# R2R.net
KiCad netlist of a schematic drawn in EAGLE
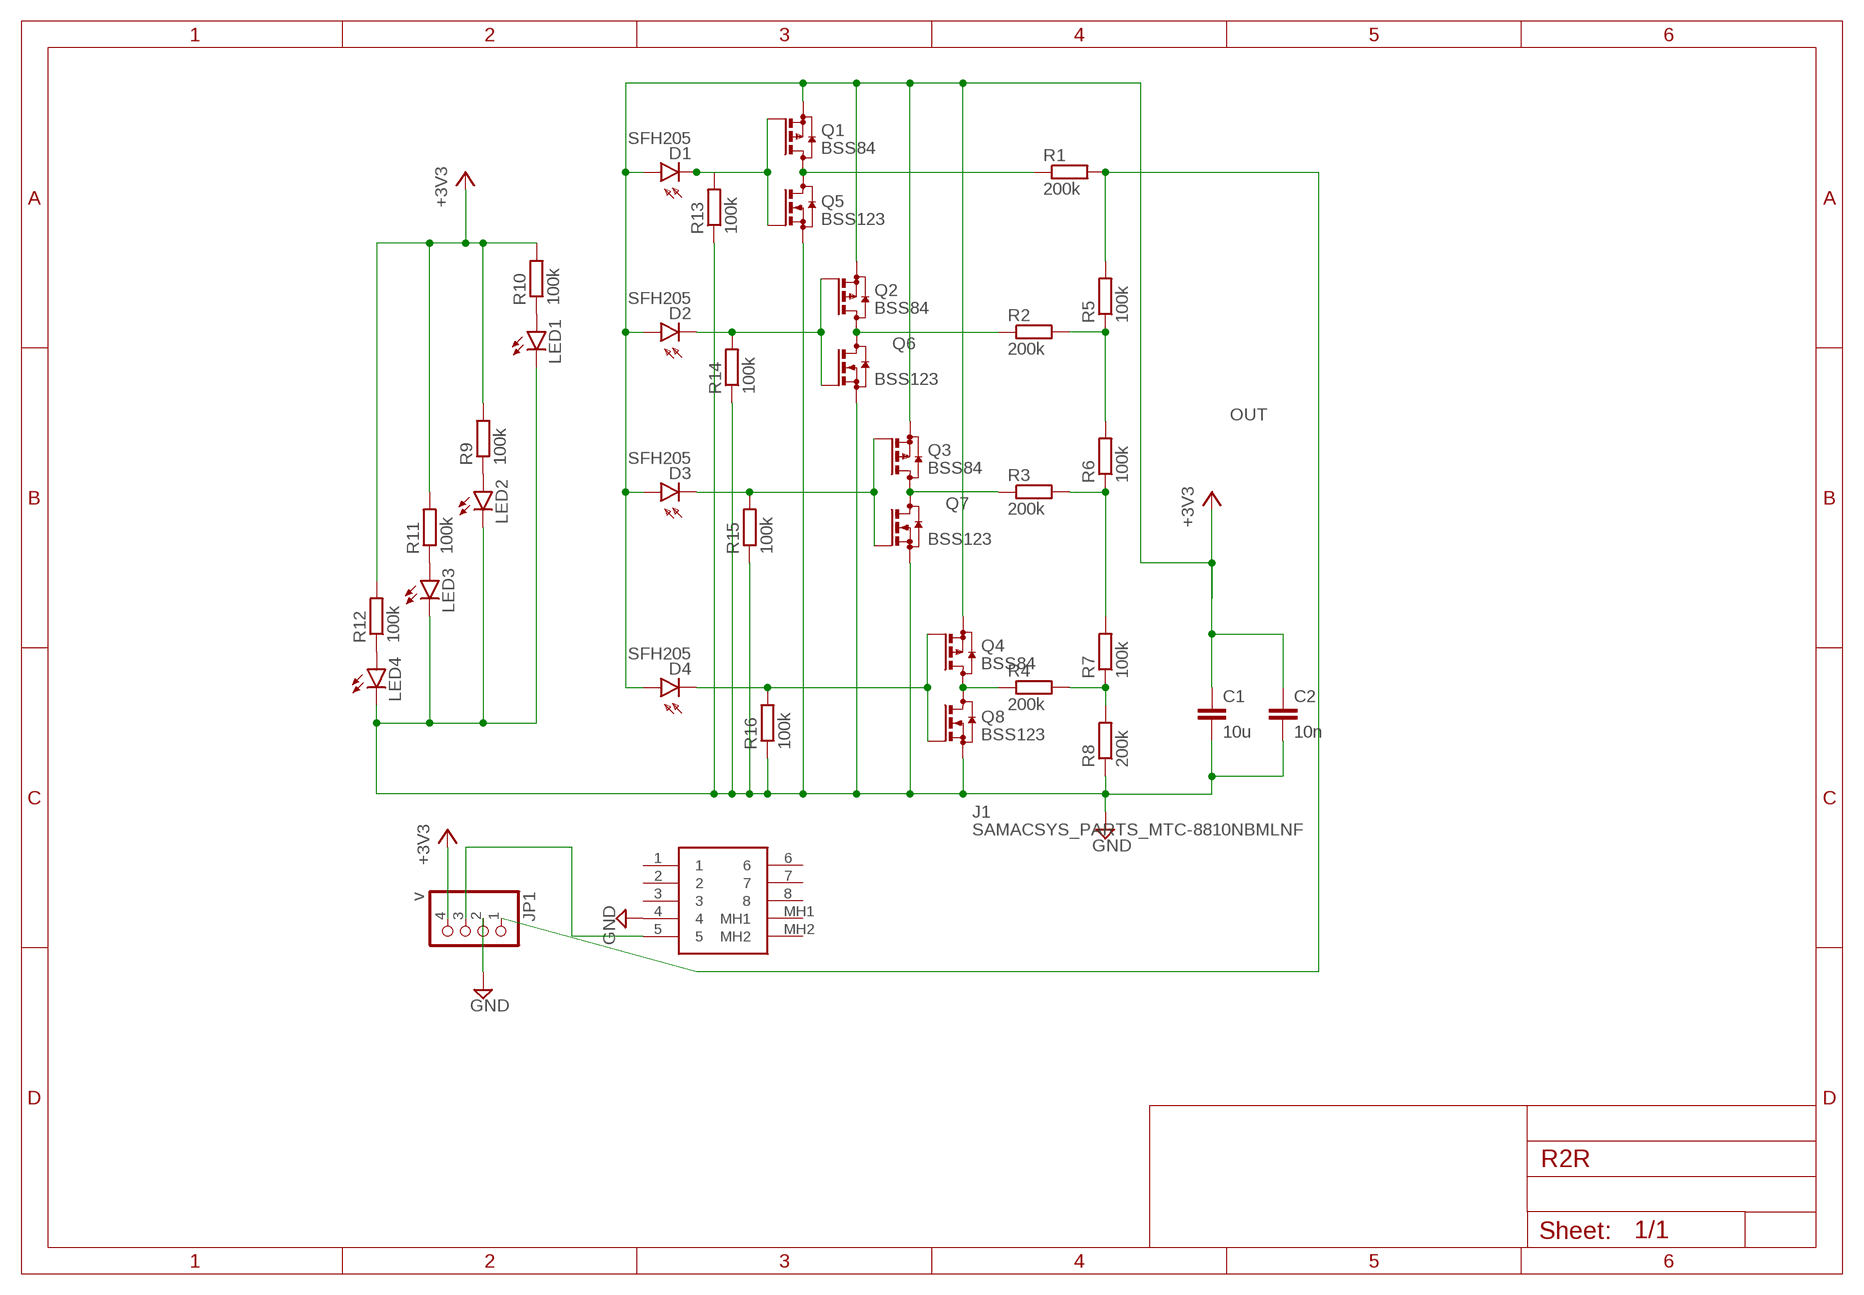
[diagram p0: schematic, sheet 1]

(export (version "E")
  (design (tool "Eeschema 10.0.6"))
  (components
    (comp (ref "C1")
      (value "10u")
      (footprint "eagle-import:C0805")
      (libsource (lib "eagle-import") (part "C-EUC0805"))
    )
    (comp (ref "C2")
      (value "10n")
      (footprint "eagle-import:C0805")
      (libsource (lib "eagle-import") (part "C-EUC0805"))
    )
    (comp (ref "D1")
      (value "SFH205")
      (footprint "eagle-import:SFH205")
      (libsource (lib "eagle-import") (part "SFH205"))
    )
    (comp (ref "D2")
      (value "SFH205")
      (footprint "eagle-import:SFH205")
      (libsource (lib "eagle-import") (part "SFH205"))
    )
    (comp (ref "D3")
      (value "SFH205")
      (footprint "eagle-import:SFH205")
      (libsource (lib "eagle-import") (part "SFH205"))
    )
    (comp (ref "D4")
      (value "SFH205")
      (footprint "eagle-import:SFH205")
      (libsource (lib "eagle-import") (part "SFH205"))
    )
    (comp (ref "J1")
      (value "SAMACSYS_PARTS_MTC-8810NBMLNF")
      (footprint "eagle-import:SAMACSYS_PARTS_MTC8810NBMLNF")
      (fields (field (name "MANUFACTURER_PART_NUMBER") "MTC-8810NBMLNF"))
      (libsource (lib "eagle-import") (part "SAMACSYS_PARTS_MTC-8810NBMLNF"))
    )
    (comp (ref "JP1")
      (value "v")
      (footprint "eagle-import:1X04")
      (libsource (lib "eagle-import") (part "PINHD-1X4"))
    )
    (comp (ref "LED1")
      (value "LED3MM")
      (footprint "eagle-import:LED3MM")
      (libsource (lib "eagle-import") (part "LED3MM"))
    )
    (comp (ref "LED2")
      (value "LED3MM")
      (footprint "eagle-import:LED3MM")
      (libsource (lib "eagle-import") (part "LED3MM"))
    )
    (comp (ref "LED3")
      (value "LED3MM")
      (footprint "eagle-import:LED3MM")
      (libsource (lib "eagle-import") (part "LED3MM"))
    )
    (comp (ref "LED4")
      (value "LED3MM")
      (footprint "eagle-import:LED3MM")
      (libsource (lib "eagle-import") (part "LED3MM"))
    )
    (comp (ref "Q1")
      (value "BSS84")
      (footprint "eagle-import:SOT23")
      (libsource (lib "eagle-import") (part "BSS84"))
    )
    (comp (ref "Q2")
      (value "BSS84")
      (footprint "eagle-import:SOT23")
      (libsource (lib "eagle-import") (part "BSS84"))
    )
    (comp (ref "Q3")
      (value "BSS84")
      (footprint "eagle-import:SOT23")
      (libsource (lib "eagle-import") (part "BSS84"))
    )
    (comp (ref "Q4")
      (value "BSS84")
      (footprint "eagle-import:SOT23")
      (libsource (lib "eagle-import") (part "BSS84"))
    )
    (comp (ref "Q5")
      (value "BSS123")
      (footprint "eagle-import:SOT23")
      (libsource (lib "eagle-import") (part "BSS123"))
    )
    (comp (ref "Q6")
      (value "BSS123")
      (footprint "eagle-import:SOT23")
      (libsource (lib "eagle-import") (part "BSS123"))
    )
    (comp (ref "Q7")
      (value "BSS123")
      (footprint "eagle-import:SOT23")
      (libsource (lib "eagle-import") (part "BSS123"))
    )
    (comp (ref "Q8")
      (value "BSS123")
      (footprint "eagle-import:SOT23")
      (libsource (lib "eagle-import") (part "BSS123"))
    )
    (comp (ref "R1")
      (value "200k")
      (footprint "eagle-import:R1206")
      (libsource (lib "eagle-import") (part "R-EU_R1206"))
    )
    (comp (ref "R2")
      (value "200k")
      (footprint "eagle-import:R1206")
      (libsource (lib "eagle-import") (part "R-EU_R1206"))
    )
    (comp (ref "R3")
      (value "200k")
      (footprint "eagle-import:R1206")
      (libsource (lib "eagle-import") (part "R-EU_R1206"))
    )
    (comp (ref "R4")
      (value "200k")
      (footprint "eagle-import:R1206")
      (libsource (lib "eagle-import") (part "R-EU_R1206"))
    )
    (comp (ref "R5")
      (value "100k")
      (footprint "eagle-import:R1206")
      (libsource (lib "eagle-import") (part "R-EU_R1206"))
    )
    (comp (ref "R6")
      (value "100k")
      (footprint "eagle-import:R1206")
      (libsource (lib "eagle-import") (part "R-EU_R1206"))
    )
    (comp (ref "R7")
      (value "100k")
      (footprint "eagle-import:R1206")
      (libsource (lib "eagle-import") (part "R-EU_R1206"))
    )
    (comp (ref "R8")
      (value "200k")
      (footprint "eagle-import:R1206")
      (libsource (lib "eagle-import") (part "R-EU_R1206"))
    )
    (comp (ref "R9")
      (value "100k")
      (footprint "eagle-import:R1206")
      (libsource (lib "eagle-import") (part "R-EU_R1206"))
    )
    (comp (ref "R10")
      (value "100k")
      (footprint "eagle-import:R1206")
      (libsource (lib "eagle-import") (part "R-EU_R1206"))
    )
    (comp (ref "R11")
      (value "100k")
      (footprint "eagle-import:R1206")
      (libsource (lib "eagle-import") (part "R-EU_R1206"))
    )
    (comp (ref "R12")
      (value "100k")
      (footprint "eagle-import:R1206")
      (libsource (lib "eagle-import") (part "R-EU_R1206"))
    )
    (comp (ref "R13")
      (value "100k")
      (footprint "eagle-import:R1206")
      (libsource (lib "eagle-import") (part "R-EU_R1206"))
    )
    (comp (ref "R14")
      (value "100k")
      (footprint "eagle-import:R1206")
      (libsource (lib "eagle-import") (part "R-EU_R1206"))
    )
    (comp (ref "R15")
      (value "100k")
      (footprint "eagle-import:R1206")
      (libsource (lib "eagle-import") (part "R-EU_R1206"))
    )
    (comp (ref "R16")
      (value "100k")
      (footprint "eagle-import:R1206")
      (libsource (lib "eagle-import") (part "R-EU_R1206"))
    )
  )
  (nets
    (net (code "1") (name "+3V3") (class "Default")
      (node (ref "C1") (pin "1") (pinfunction "1_1") (pintype "passive"))
      (node (ref "C2") (pin "1") (pinfunction "1_1") (pintype "passive"))
      (node (ref "D1") (pin "A") (pinfunction "A_A") (pintype "passive"))
      (node (ref "D2") (pin "A") (pinfunction "A_A") (pintype "passive"))
      (node (ref "D3") (pin "A") (pinfunction "A_A") (pintype "passive"))
      (node (ref "D4") (pin "A") (pinfunction "A_A") (pintype "passive"))
      (node (ref "JP1") (pin "4") (pinfunction "4_4") (pintype "passive"))
      (node (ref "Q1") (pin "2") (pinfunction "S_2") (pintype "passive"))
      (node (ref "Q2") (pin "2") (pinfunction "S_2") (pintype "passive"))
      (node (ref "Q3") (pin "2") (pinfunction "S_2") (pintype "passive"))
      (node (ref "Q4") (pin "2") (pinfunction "S_2") (pintype "passive"))
      (node (ref "R10") (pin "2") (pinfunction "2_2") (pintype "passive"))
      (node (ref "R11") (pin "2") (pinfunction "2_2") (pintype "passive"))
      (node (ref "R12") (pin "2") (pinfunction "2_2") (pintype "passive"))
      (node (ref "R9") (pin "2") (pinfunction "2_2") (pintype "passive"))
    )
    (net (code "2") (name "/OUT") (class "Default")
      (node (ref "JP1") (pin "1") (pinfunction "1_1") (pintype "passive"))
      (node (ref "R1") (pin "2") (pinfunction "2_2") (pintype "passive"))
      (node (ref "R5") (pin "2") (pinfunction "2_2") (pintype "passive"))
    )
    (net (code "3") (name "GND") (class "Default")
      (node (ref "C1") (pin "2") (pinfunction "2_2") (pintype "passive"))
      (node (ref "C2") (pin "2") (pinfunction "2_2") (pintype "passive"))
      (node (ref "J1") (pin "4") (pinfunction "4_4") (pintype "bidirectional"))
      (node (ref "JP1") (pin "2") (pinfunction "2_2") (pintype "passive"))
      (node (ref "LED1") (pin "K") (pinfunction "C_K") (pintype "passive"))
      (node (ref "LED2") (pin "K") (pinfunction "C_K") (pintype "passive"))
      (node (ref "LED3") (pin "K") (pinfunction "C_K") (pintype "passive"))
      (node (ref "LED4") (pin "K") (pinfunction "C_K") (pintype "passive"))
      (node (ref "Q5") (pin "2") (pinfunction "S_2") (pintype "passive"))
      (node (ref "Q6") (pin "2") (pinfunction "S_2") (pintype "passive"))
      (node (ref "Q7") (pin "2") (pinfunction "S_2") (pintype "passive"))
      (node (ref "Q8") (pin "2") (pinfunction "S_2") (pintype "passive"))
      (node (ref "R13") (pin "1") (pinfunction "1_1") (pintype "passive"))
      (node (ref "R14") (pin "1") (pinfunction "1_1") (pintype "passive"))
      (node (ref "R15") (pin "1") (pinfunction "1_1") (pintype "passive"))
      (node (ref "R16") (pin "1") (pinfunction "1_1") (pintype "passive"))
      (node (ref "R8") (pin "1") (pinfunction "1_1") (pintype "passive"))
    )
    (net (code "4") (name "Net-(D1-C)") (class "Default")
      (node (ref "D1") (pin "K") (pinfunction "C_K") (pintype "passive"))
      (node (ref "Q1") (pin "1") (pinfunction "G_1") (pintype "passive"))
      (node (ref "Q5") (pin "1") (pinfunction "G_1") (pintype "passive"))
      (node (ref "R13") (pin "2") (pinfunction "2_2") (pintype "passive"))
    )
    (net (code "5") (name "Net-(D2-C)") (class "Default")
      (node (ref "D2") (pin "K") (pinfunction "C_K") (pintype "passive"))
      (node (ref "Q2") (pin "1") (pinfunction "G_1") (pintype "passive"))
      (node (ref "Q6") (pin "1") (pinfunction "G_1") (pintype "passive"))
      (node (ref "R14") (pin "2") (pinfunction "2_2") (pintype "passive"))
    )
    (net (code "6") (name "Net-(D3-C)") (class "Default")
      (node (ref "D3") (pin "K") (pinfunction "C_K") (pintype "passive"))
      (node (ref "Q3") (pin "1") (pinfunction "G_1") (pintype "passive"))
      (node (ref "Q7") (pin "1") (pinfunction "G_1") (pintype "passive"))
      (node (ref "R15") (pin "2") (pinfunction "2_2") (pintype "passive"))
    )
    (net (code "7") (name "Net-(D4-C)") (class "Default")
      (node (ref "D4") (pin "K") (pinfunction "C_K") (pintype "passive"))
      (node (ref "Q4") (pin "1") (pinfunction "G_1") (pintype "passive"))
      (node (ref "Q8") (pin "1") (pinfunction "G_1") (pintype "passive"))
      (node (ref "R16") (pin "2") (pinfunction "2_2") (pintype "passive"))
    )
    (net (code "8") (name "Net-(J1-Pad5)") (class "Default")
      (node (ref "J1") (pin "5") (pinfunction "5_5") (pintype "bidirectional"))
      (node (ref "JP1") (pin "3") (pinfunction "3_3") (pintype "passive"))
    )
    (net (code "9") (name "Net-(LED1-PadA)") (class "Default")
      (node (ref "LED1") (pin "A") (pinfunction "A_A") (pintype "passive"))
      (node (ref "R10") (pin "1") (pinfunction "1_1") (pintype "passive"))
    )
    (net (code "10") (name "Net-(LED2-PadA)") (class "Default")
      (node (ref "LED2") (pin "A") (pinfunction "A_A") (pintype "passive"))
      (node (ref "R9") (pin "1") (pinfunction "1_1") (pintype "passive"))
    )
    (net (code "11") (name "Net-(LED3-PadA)") (class "Default")
      (node (ref "LED3") (pin "A") (pinfunction "A_A") (pintype "passive"))
      (node (ref "R11") (pin "1") (pinfunction "1_1") (pintype "passive"))
    )
    (net (code "12") (name "Net-(LED4-PadA)") (class "Default")
      (node (ref "LED4") (pin "A") (pinfunction "A_A") (pintype "passive"))
      (node (ref "R12") (pin "1") (pinfunction "1_1") (pintype "passive"))
    )
    (net (code "13") (name "Net-(Q1-D)") (class "Default")
      (node (ref "Q1") (pin "3") (pinfunction "D_3") (pintype "passive"))
      (node (ref "Q5") (pin "3") (pinfunction "D_3") (pintype "passive"))
      (node (ref "R1") (pin "1") (pinfunction "1_1") (pintype "passive"))
    )
    (net (code "14") (name "Net-(Q2-D)") (class "Default")
      (node (ref "Q2") (pin "3") (pinfunction "D_3") (pintype "passive"))
      (node (ref "Q6") (pin "3") (pinfunction "D_3") (pintype "passive"))
      (node (ref "R2") (pin "1") (pinfunction "1_1") (pintype "passive"))
    )
    (net (code "15") (name "Net-(Q3-D)") (class "Default")
      (node (ref "Q3") (pin "3") (pinfunction "D_3") (pintype "passive"))
      (node (ref "Q7") (pin "3") (pinfunction "D_3") (pintype "passive"))
      (node (ref "R3") (pin "1") (pinfunction "1_1") (pintype "passive"))
    )
    (net (code "16") (name "Net-(Q4-D)") (class "Default")
      (node (ref "Q4") (pin "3") (pinfunction "D_3") (pintype "passive"))
      (node (ref "Q8") (pin "3") (pinfunction "D_3") (pintype "passive"))
      (node (ref "R4") (pin "1") (pinfunction "1_1") (pintype "passive"))
    )
    (net (code "17") (name "Net-(R2-Pad2)") (class "Default")
      (node (ref "R2") (pin "2") (pinfunction "2_2") (pintype "passive"))
      (node (ref "R5") (pin "1") (pinfunction "1_1") (pintype "passive"))
      (node (ref "R6") (pin "2") (pinfunction "2_2") (pintype "passive"))
    )
    (net (code "18") (name "Net-(R3-Pad2)") (class "Default")
      (node (ref "R3") (pin "2") (pinfunction "2_2") (pintype "passive"))
      (node (ref "R6") (pin "1") (pinfunction "1_1") (pintype "passive"))
      (node (ref "R7") (pin "2") (pinfunction "2_2") (pintype "passive"))
    )
    (net (code "19") (name "Net-(R4-Pad2)") (class "Default")
      (node (ref "R4") (pin "2") (pinfunction "2_2") (pintype "passive"))
      (node (ref "R7") (pin "1") (pinfunction "1_1") (pintype "passive"))
      (node (ref "R8") (pin "2") (pinfunction "2_2") (pintype "passive"))
    )
    (net (code "20") (name "unconnected-(J1-Pad1)") (class "Default")
      (node (ref "J1") (pin "1") (pinfunction "1_1") (pintype "bidirectional"))
    )
    (net (code "21") (name "unconnected-(J1-Pad2)") (class "Default")
      (node (ref "J1") (pin "2") (pinfunction "2_2") (pintype "bidirectional"))
    )
    (net (code "22") (name "unconnected-(J1-Pad3)") (class "Default")
      (node (ref "J1") (pin "3") (pinfunction "3_3") (pintype "bidirectional"))
    )
    (net (code "23") (name "unconnected-(J1-Pad6)") (class "Default")
      (node (ref "J1") (pin "6") (pinfunction "6_6") (pintype "bidirectional"))
    )
    (net (code "24") (name "unconnected-(J1-Pad7)") (class "Default")
      (node (ref "J1") (pin "7") (pinfunction "7_7") (pintype "bidirectional"))
    )
    (net (code "25") (name "unconnected-(J1-Pad8)") (class "Default")
      (node (ref "J1") (pin "8") (pinfunction "8_8") (pintype "bidirectional"))
    )
    (net (code "26") (name "unconnected-(J1-PadMH1)") (class "Default")
      (node (ref "J1") (pin "MH1") (pinfunction "MH1_MH1") (pintype "bidirectional"))
    )
    (net (code "27") (name "unconnected-(J1-PadMH2)") (class "Default")
      (node (ref "J1") (pin "MH2") (pinfunction "MH2_MH2") (pintype "bidirectional"))
    )
  )
)
